# M212B.net
KiCad netlist of a schematic drawn in EAGLE
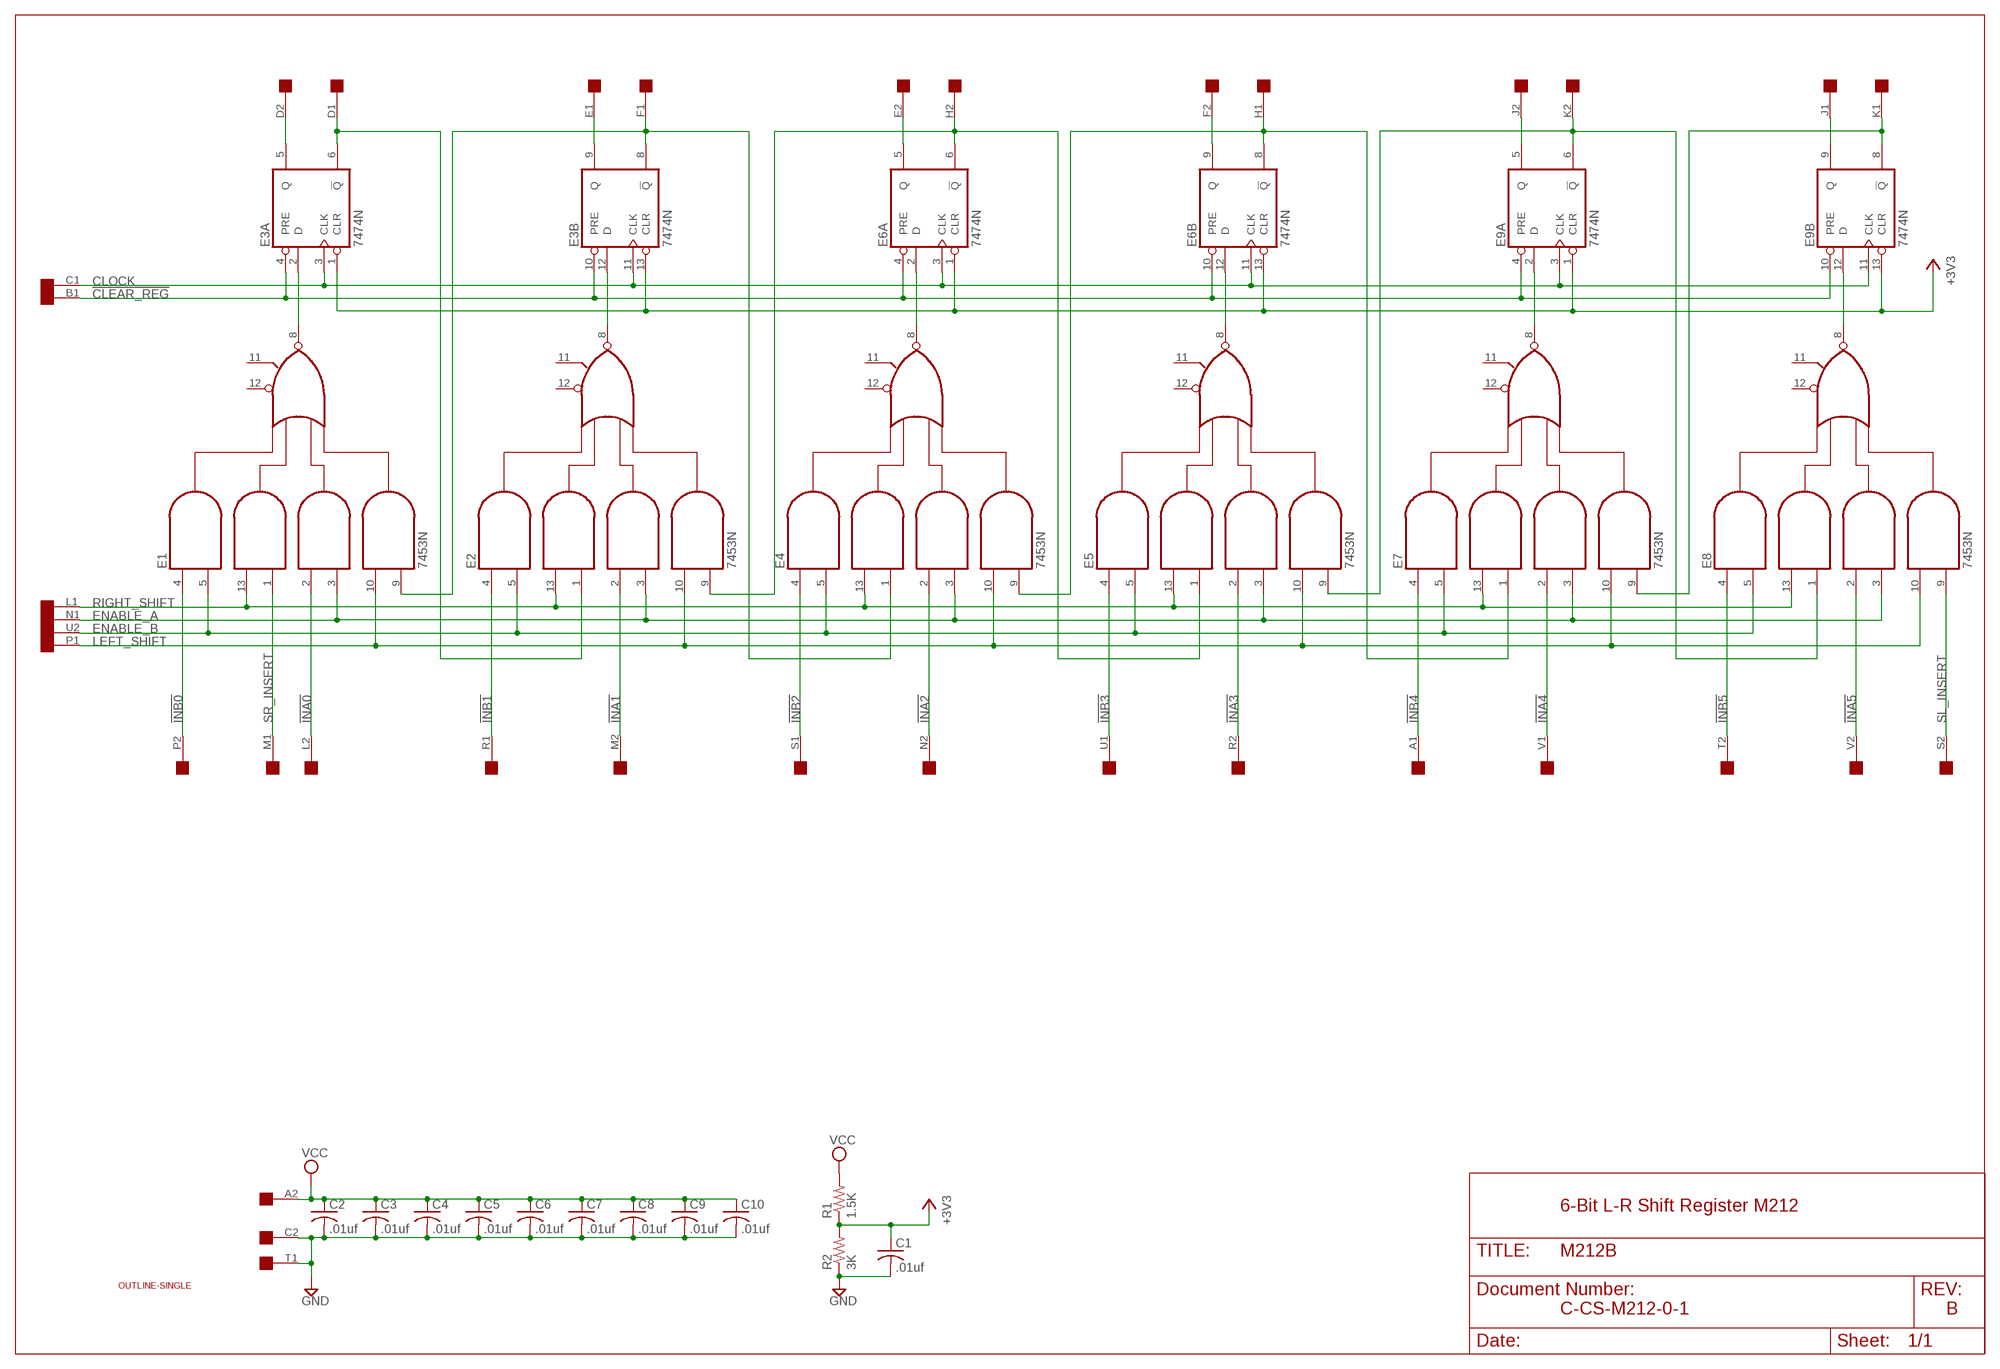
[diagram p0: schematic, sheet 1]

(export (version "E")
  (design (tool "Eeschema 10.0.6"))
  (components
    (comp (ref "C1")
      (value ".01uf")
      (footprint "eagle-import:C050-025X075")
      (libsource (lib "eagle-import") (part "C-US050-025X075"))
    )
    (comp (ref "C2")
      (value ".01uf")
      (footprint "eagle-import:C075-032X103")
      (libsource (lib "eagle-import") (part "C-US075-032X103"))
    )
    (comp (ref "C3")
      (value ".01uf")
      (footprint "eagle-import:C075-032X103")
      (libsource (lib "eagle-import") (part "C-US075-032X103"))
    )
    (comp (ref "C4")
      (value ".01uf")
      (footprint "eagle-import:C075-032X103")
      (libsource (lib "eagle-import") (part "C-US075-032X103"))
    )
    (comp (ref "C5")
      (value ".01uf")
      (footprint "eagle-import:C075-032X103")
      (libsource (lib "eagle-import") (part "C-US075-032X103"))
    )
    (comp (ref "C6")
      (value ".01uf")
      (footprint "eagle-import:C075-032X103")
      (libsource (lib "eagle-import") (part "C-US075-032X103"))
    )
    (comp (ref "C7")
      (value ".01uf")
      (footprint "eagle-import:C075-032X103")
      (libsource (lib "eagle-import") (part "C-US075-032X103"))
    )
    (comp (ref "C8")
      (value ".01uf")
      (footprint "eagle-import:C075-032X103")
      (libsource (lib "eagle-import") (part "C-US075-032X103"))
    )
    (comp (ref "C9")
      (value ".01uf")
      (footprint "eagle-import:C075-032X103")
      (libsource (lib "eagle-import") (part "C-US075-032X103"))
    )
    (comp (ref "C10")
      (value ".01uf")
      (footprint "eagle-import:C075-032X103")
      (libsource (lib "eagle-import") (part "C-US075-032X103"))
    )
    (comp (ref "E1")
      (value "7453N")
      (footprint "eagle-import:DIL14")
      (libsource (lib "eagle-import") (part "7453N"))
    )
    (comp (ref "E2")
      (value "7453N")
      (footprint "eagle-import:DIL14")
      (libsource (lib "eagle-import") (part "7453N"))
    )
    (comp (ref "E3")
      (value "7474N")
      (footprint "eagle-import:DIL14")
      (libsource (lib "eagle-import") (part "7474NS"))
    )
    (comp (ref "E4")
      (value "7453N")
      (footprint "eagle-import:DIL14")
      (libsource (lib "eagle-import") (part "7453N"))
    )
    (comp (ref "E5")
      (value "7453N")
      (footprint "eagle-import:DIL14")
      (libsource (lib "eagle-import") (part "7453N"))
    )
    (comp (ref "E6")
      (value "7474N")
      (footprint "eagle-import:DIL14")
      (libsource (lib "eagle-import") (part "7474NS"))
    )
    (comp (ref "E7")
      (value "7453N")
      (footprint "eagle-import:DIL14")
      (libsource (lib "eagle-import") (part "7453N"))
    )
    (comp (ref "E8")
      (value "7453N")
      (footprint "eagle-import:DIL14")
      (libsource (lib "eagle-import") (part "7453N"))
    )
    (comp (ref "E9")
      (value "7474N")
      (footprint "eagle-import:DIL14")
      (libsource (lib "eagle-import") (part "7474NS"))
    )
    (comp (ref "EDGE1")
      (value "EDGE-2CONNECTOR")
      (footprint "eagle-import:EDGE-CON2")
      (libsource (lib "eagle-import") (part "EDGE-2CONNECTOR"))
    )
    (comp (ref "R1")
      (value "1.5K")
      (footprint "eagle-import:0207_10")
      (libsource (lib "eagle-import") (part "R-US_0207/10"))
    )
    (comp (ref "R2")
      (value "3K")
      (footprint "eagle-import:0207_10")
      (libsource (lib "eagle-import") (part "R-US_0207/10"))
    )
    (comp (ref "U$1")
      (value "OUTLINE-SINGLE")
      (footprint "eagle-import:SINGLE")
      (libsource (lib "eagle-import") (part "OUTLINE-SINGLE"))
    )
  )
  (nets
    (net (code "1") (name "+3V3") (class "Default")
      (node (ref "C1") (pin "1") (pinfunction "1_1") (pintype "passive"))
      (node (ref "E3") (pin "1") (pinfunction "CLR_1") (pintype "input"))
      (node (ref "E3") (pin "13") (pinfunction "CLR_13") (pintype "input"))
      (node (ref "E6") (pin "1") (pinfunction "CLR_1") (pintype "input"))
      (node (ref "E6") (pin "13") (pinfunction "CLR_13") (pintype "input"))
      (node (ref "E9") (pin "1") (pinfunction "CLR_1") (pintype "input"))
      (node (ref "E9") (pin "13") (pinfunction "CLR_13") (pintype "input"))
      (node (ref "R1") (pin "1") (pinfunction "1_1") (pintype "passive"))
      (node (ref "R2") (pin "2") (pinfunction "2_2") (pintype "passive"))
    )
    (net (code "2") (name "/CLOCK") (class "Default")
      (node (ref "E3") (pin "11") (pinfunction "CLK_11") (pintype "input"))
      (node (ref "E3") (pin "3") (pinfunction "CLK_3") (pintype "input"))
      (node (ref "E6") (pin "11") (pinfunction "CLK_11") (pintype "input"))
      (node (ref "E6") (pin "3") (pinfunction "CLK_3") (pintype "input"))
      (node (ref "E9") (pin "11") (pinfunction "CLK_11") (pintype "input"))
      (node (ref "E9") (pin "3") (pinfunction "CLK_3") (pintype "input"))
      (node (ref "EDGE1") (pin "C1") (pinfunction "1_C1") (pintype "bidirectional"))
    )
    (net (code "3") (name "/ENABLE_A") (class "Default")
      (node (ref "E1") (pin "3") (pinfunction "I6_3") (pintype "input"))
      (node (ref "E2") (pin "3") (pinfunction "I6_3") (pintype "input"))
      (node (ref "E4") (pin "3") (pinfunction "I6_3") (pintype "input"))
      (node (ref "E5") (pin "3") (pinfunction "I6_3") (pintype "input"))
      (node (ref "E7") (pin "3") (pinfunction "I6_3") (pintype "input"))
      (node (ref "E8") (pin "3") (pinfunction "I6_3") (pintype "input"))
      (node (ref "EDGE1") (pin "N1") (pinfunction "1_N1") (pintype "bidirectional"))
    )
    (net (code "4") (name "/ENABLE_B") (class "Default")
      (node (ref "E1") (pin "5") (pinfunction "I2_5") (pintype "input"))
      (node (ref "E2") (pin "5") (pinfunction "I2_5") (pintype "input"))
      (node (ref "E4") (pin "5") (pinfunction "I2_5") (pintype "input"))
      (node (ref "E5") (pin "5") (pinfunction "I2_5") (pintype "input"))
      (node (ref "E7") (pin "5") (pinfunction "I2_5") (pintype "input"))
      (node (ref "E8") (pin "5") (pinfunction "I2_5") (pintype "input"))
      (node (ref "EDGE1") (pin "U2") (pinfunction "1_U2") (pintype "bidirectional"))
    )
    (net (code "5") (name "/LEFT_SHIFT") (class "Default")
      (node (ref "E1") (pin "10") (pinfunction "I7_10") (pintype "input"))
      (node (ref "E2") (pin "10") (pinfunction "I7_10") (pintype "input"))
      (node (ref "E4") (pin "10") (pinfunction "I7_10") (pintype "input"))
      (node (ref "E5") (pin "10") (pinfunction "I7_10") (pintype "input"))
      (node (ref "E7") (pin "10") (pinfunction "I7_10") (pintype "input"))
      (node (ref "E8") (pin "10") (pinfunction "I7_10") (pintype "input"))
      (node (ref "EDGE1") (pin "P1") (pinfunction "1_P1") (pintype "bidirectional"))
    )
    (net (code "6") (name "/RIGHT_SHIFT") (class "Default")
      (node (ref "E1") (pin "13") (pinfunction "I3_13") (pintype "input"))
      (node (ref "E2") (pin "13") (pinfunction "I3_13") (pintype "input"))
      (node (ref "E4") (pin "13") (pinfunction "I3_13") (pintype "input"))
      (node (ref "E5") (pin "13") (pinfunction "I3_13") (pintype "input"))
      (node (ref "E7") (pin "13") (pinfunction "I3_13") (pintype "input"))
      (node (ref "E8") (pin "13") (pinfunction "I3_13") (pintype "input"))
      (node (ref "EDGE1") (pin "L1") (pinfunction "1_L1") (pintype "bidirectional"))
    )
    (net (code "7") (name "/SL_INSERT") (class "Default")
      (node (ref "E8") (pin "9") (pinfunction "I8_9") (pintype "input"))
      (node (ref "EDGE1") (pin "S2") (pinfunction "1_S2") (pintype "bidirectional"))
    )
    (net (code "8") (name "/SR_INSERT") (class "Default")
      (node (ref "E1") (pin "1") (pinfunction "I4_1") (pintype "input"))
      (node (ref "EDGE1") (pin "M1") (pinfunction "1_M1") (pintype "bidirectional"))
    )
    (net (code "9") (name "/~{CLEAR_REG}") (class "Default")
      (node (ref "E3") (pin "10") (pinfunction "PRE_10") (pintype "input"))
      (node (ref "E3") (pin "4") (pinfunction "PRE_4") (pintype "input"))
      (node (ref "E6") (pin "10") (pinfunction "PRE_10") (pintype "input"))
      (node (ref "E6") (pin "4") (pinfunction "PRE_4") (pintype "input"))
      (node (ref "E9") (pin "10") (pinfunction "PRE_10") (pintype "input"))
      (node (ref "E9") (pin "4") (pinfunction "PRE_4") (pintype "input"))
      (node (ref "EDGE1") (pin "B1") (pinfunction "1_B1") (pintype "bidirectional"))
    )
    (net (code "10") (name "/~{INA0}") (class "Default")
      (node (ref "E1") (pin "2") (pinfunction "I5_2") (pintype "input"))
      (node (ref "EDGE1") (pin "L2") (pinfunction "1_L2") (pintype "bidirectional"))
    )
    (net (code "11") (name "/~{INA1}") (class "Default")
      (node (ref "E2") (pin "2") (pinfunction "I5_2") (pintype "input"))
      (node (ref "EDGE1") (pin "M2") (pinfunction "1_M2") (pintype "bidirectional"))
    )
    (net (code "12") (name "/~{INA2}") (class "Default")
      (node (ref "E4") (pin "2") (pinfunction "I5_2") (pintype "input"))
      (node (ref "EDGE1") (pin "N2") (pinfunction "1_N2") (pintype "bidirectional"))
    )
    (net (code "13") (name "/~{INA3}") (class "Default")
      (node (ref "E5") (pin "2") (pinfunction "I5_2") (pintype "input"))
      (node (ref "EDGE1") (pin "R2") (pinfunction "1_R2") (pintype "bidirectional"))
    )
    (net (code "14") (name "/~{INA4}") (class "Default")
      (node (ref "E7") (pin "2") (pinfunction "I5_2") (pintype "input"))
      (node (ref "EDGE1") (pin "V1") (pinfunction "1_V1") (pintype "bidirectional"))
    )
    (net (code "15") (name "/~{INA5}") (class "Default")
      (node (ref "E8") (pin "2") (pinfunction "I5_2") (pintype "input"))
      (node (ref "EDGE1") (pin "V2") (pinfunction "1_V2") (pintype "bidirectional"))
    )
    (net (code "16") (name "/~{INB0}") (class "Default")
      (node (ref "E1") (pin "4") (pinfunction "I1_4") (pintype "input"))
      (node (ref "EDGE1") (pin "P2") (pinfunction "1_P2") (pintype "bidirectional"))
    )
    (net (code "17") (name "/~{INB1}") (class "Default")
      (node (ref "E2") (pin "4") (pinfunction "I1_4") (pintype "input"))
      (node (ref "EDGE1") (pin "R1") (pinfunction "1_R1") (pintype "bidirectional"))
    )
    (net (code "18") (name "/~{INB2}") (class "Default")
      (node (ref "E4") (pin "4") (pinfunction "I1_4") (pintype "input"))
      (node (ref "EDGE1") (pin "S1") (pinfunction "1_S1") (pintype "bidirectional"))
    )
    (net (code "19") (name "/~{INB3}") (class "Default")
      (node (ref "E5") (pin "4") (pinfunction "I1_4") (pintype "input"))
      (node (ref "EDGE1") (pin "U1") (pinfunction "1_U1") (pintype "bidirectional"))
    )
    (net (code "20") (name "/~{INB4}") (class "Default")
      (node (ref "E7") (pin "4") (pinfunction "I1_4") (pintype "input"))
      (node (ref "EDGE1") (pin "A1") (pinfunction "1_A1") (pintype "bidirectional"))
    )
    (net (code "21") (name "/~{INB5}") (class "Default")
      (node (ref "E8") (pin "4") (pinfunction "I1_4") (pintype "input"))
      (node (ref "EDGE1") (pin "T2") (pinfunction "1_T2") (pintype "bidirectional"))
    )
    (net (code "22") (name "GND") (class "Default")
      (node (ref "C1") (pin "2") (pinfunction "2_2") (pintype "passive"))
      (node (ref "C10") (pin "2") (pinfunction "2_2") (pintype "passive"))
      (node (ref "C2") (pin "2") (pinfunction "2_2") (pintype "passive"))
      (node (ref "C3") (pin "2") (pinfunction "2_2") (pintype "passive"))
      (node (ref "C4") (pin "2") (pinfunction "2_2") (pintype "passive"))
      (node (ref "C5") (pin "2") (pinfunction "2_2") (pintype "passive"))
      (node (ref "C6") (pin "2") (pinfunction "2_2") (pintype "passive"))
      (node (ref "C7") (pin "2") (pinfunction "2_2") (pintype "passive"))
      (node (ref "C8") (pin "2") (pinfunction "2_2") (pintype "passive"))
      (node (ref "C9") (pin "2") (pinfunction "2_2") (pintype "passive"))
      (node (ref "EDGE1") (pin "C2") (pinfunction "1_C2") (pintype "bidirectional"))
      (node (ref "EDGE1") (pin "T1") (pinfunction "1_T1") (pintype "bidirectional"))
      (node (ref "R2") (pin "1") (pinfunction "1_1") (pintype "passive"))
    )
    (net (code "23") (name "Net-(E1A-I8)") (class "Default")
      (node (ref "E1") (pin "9") (pinfunction "I8_9") (pintype "input"))
      (node (ref "E3") (pin "8") (pinfunction "~{Q}_8") (pintype "output"))
      (node (ref "E4") (pin "1") (pinfunction "I4_1") (pintype "input"))
      (node (ref "EDGE1") (pin "F1") (pinfunction "1_F1") (pintype "bidirectional"))
    )
    (net (code "24") (name "Net-(E1A-O)") (class "Default")
      (node (ref "E1") (pin "8") (pinfunction "O_8") (pintype "output"))
      (node (ref "E3") (pin "2") (pinfunction "D_2") (pintype "input"))
    )
    (net (code "25") (name "Net-(E2A-I4)") (class "Default")
      (node (ref "E2") (pin "1") (pinfunction "I4_1") (pintype "input"))
      (node (ref "E3") (pin "6") (pinfunction "~{Q}_6") (pintype "output"))
      (node (ref "EDGE1") (pin "D1") (pinfunction "1_D1") (pintype "bidirectional"))
    )
    (net (code "26") (name "Net-(E2A-I8)") (class "Default")
      (node (ref "E2") (pin "9") (pinfunction "I8_9") (pintype "input"))
      (node (ref "E5") (pin "1") (pinfunction "I4_1") (pintype "input"))
      (node (ref "E6") (pin "6") (pinfunction "~{Q}_6") (pintype "output"))
      (node (ref "EDGE1") (pin "H2") (pinfunction "1_H2") (pintype "bidirectional"))
    )
    (net (code "27") (name "Net-(E2A-O)") (class "Default")
      (node (ref "E2") (pin "8") (pinfunction "O_8") (pintype "output"))
      (node (ref "E3") (pin "12") (pinfunction "D_12") (pintype "input"))
    )
    (net (code "28") (name "Net-(E3A-Q)") (class "Default")
      (node (ref "E3") (pin "5") (pinfunction "Q_5") (pintype "output"))
      (node (ref "EDGE1") (pin "D2") (pinfunction "1_D2") (pintype "bidirectional"))
    )
    (net (code "29") (name "Net-(E3B-Q)") (class "Default")
      (node (ref "E3") (pin "9") (pinfunction "Q_9") (pintype "output"))
      (node (ref "EDGE1") (pin "E1") (pinfunction "1_E1") (pintype "bidirectional"))
    )
    (net (code "30") (name "Net-(E4A-I8)") (class "Default")
      (node (ref "E4") (pin "9") (pinfunction "I8_9") (pintype "input"))
      (node (ref "E6") (pin "8") (pinfunction "~{Q}_8") (pintype "output"))
      (node (ref "E7") (pin "1") (pinfunction "I4_1") (pintype "input"))
      (node (ref "EDGE1") (pin "H1") (pinfunction "1_H1") (pintype "bidirectional"))
    )
    (net (code "31") (name "Net-(E4A-O)") (class "Default")
      (node (ref "E4") (pin "8") (pinfunction "O_8") (pintype "output"))
      (node (ref "E6") (pin "2") (pinfunction "D_2") (pintype "input"))
    )
    (net (code "32") (name "Net-(E5A-I8)") (class "Default")
      (node (ref "E5") (pin "9") (pinfunction "I8_9") (pintype "input"))
      (node (ref "E8") (pin "1") (pinfunction "I4_1") (pintype "input"))
      (node (ref "E9") (pin "6") (pinfunction "~{Q}_6") (pintype "output"))
      (node (ref "EDGE1") (pin "K2") (pinfunction "1_K2") (pintype "bidirectional"))
    )
    (net (code "33") (name "Net-(E5A-O)") (class "Default")
      (node (ref "E5") (pin "8") (pinfunction "O_8") (pintype "output"))
      (node (ref "E6") (pin "12") (pinfunction "D_12") (pintype "input"))
    )
    (net (code "34") (name "Net-(E6A-Q)") (class "Default")
      (node (ref "E6") (pin "5") (pinfunction "Q_5") (pintype "output"))
      (node (ref "EDGE1") (pin "E2") (pinfunction "1_E2") (pintype "bidirectional"))
    )
    (net (code "35") (name "Net-(E6B-Q)") (class "Default")
      (node (ref "E6") (pin "9") (pinfunction "Q_9") (pintype "output"))
      (node (ref "EDGE1") (pin "F2") (pinfunction "1_F2") (pintype "bidirectional"))
    )
    (net (code "36") (name "Net-(E7A-I8)") (class "Default")
      (node (ref "E7") (pin "9") (pinfunction "I8_9") (pintype "input"))
      (node (ref "E9") (pin "8") (pinfunction "~{Q}_8") (pintype "output"))
      (node (ref "EDGE1") (pin "K1") (pinfunction "1_K1") (pintype "bidirectional"))
    )
    (net (code "37") (name "Net-(E7A-O)") (class "Default")
      (node (ref "E7") (pin "8") (pinfunction "O_8") (pintype "output"))
      (node (ref "E9") (pin "2") (pinfunction "D_2") (pintype "input"))
    )
    (net (code "38") (name "Net-(E8A-O)") (class "Default")
      (node (ref "E8") (pin "8") (pinfunction "O_8") (pintype "output"))
      (node (ref "E9") (pin "12") (pinfunction "D_12") (pintype "input"))
    )
    (net (code "39") (name "Net-(E9A-Q)") (class "Default")
      (node (ref "E9") (pin "5") (pinfunction "Q_5") (pintype "output"))
      (node (ref "EDGE1") (pin "J2") (pinfunction "1_J2") (pintype "bidirectional"))
    )
    (net (code "40") (name "Net-(E9B-Q)") (class "Default")
      (node (ref "E9") (pin "9") (pinfunction "Q_9") (pintype "output"))
      (node (ref "EDGE1") (pin "J1") (pinfunction "1_J1") (pintype "bidirectional"))
    )
    (net (code "41") (name "VCC") (class "Default")
      (node (ref "C10") (pin "1") (pinfunction "1_1") (pintype "passive"))
      (node (ref "C2") (pin "1") (pinfunction "1_1") (pintype "passive"))
      (node (ref "C3") (pin "1") (pinfunction "1_1") (pintype "passive"))
      (node (ref "C4") (pin "1") (pinfunction "1_1") (pintype "passive"))
      (node (ref "C5") (pin "1") (pinfunction "1_1") (pintype "passive"))
      (node (ref "C6") (pin "1") (pinfunction "1_1") (pintype "passive"))
      (node (ref "C7") (pin "1") (pinfunction "1_1") (pintype "passive"))
      (node (ref "C8") (pin "1") (pinfunction "1_1") (pintype "passive"))
      (node (ref "C9") (pin "1") (pinfunction "1_1") (pintype "passive"))
      (node (ref "EDGE1") (pin "A2") (pinfunction "1_A2") (pintype "bidirectional"))
      (node (ref "R1") (pin "2") (pinfunction "2_2") (pintype "passive"))
    )
    (net (code "42") (name "unconnected-(E1A-I9-Pad12)") (class "Default")
      (node (ref "E1") (pin "12") (pinfunction "I9_12") (pintype "passive"))
    )
    (net (code "43") (name "unconnected-(E1A-I10-Pad11)") (class "Default")
      (node (ref "E1") (pin "11") (pinfunction "I10_11") (pintype "passive"))
    )
    (net (code "44") (name "unconnected-(E2A-I9-Pad12)") (class "Default")
      (node (ref "E2") (pin "12") (pinfunction "I9_12") (pintype "passive"))
    )
    (net (code "45") (name "unconnected-(E2A-I10-Pad11)") (class "Default")
      (node (ref "E2") (pin "11") (pinfunction "I10_11") (pintype "passive"))
    )
    (net (code "46") (name "unconnected-(E4A-I9-Pad12)") (class "Default")
      (node (ref "E4") (pin "12") (pinfunction "I9_12") (pintype "passive"))
    )
    (net (code "47") (name "unconnected-(E4A-I10-Pad11)") (class "Default")
      (node (ref "E4") (pin "11") (pinfunction "I10_11") (pintype "passive"))
    )
    (net (code "48") (name "unconnected-(E5A-I9-Pad12)") (class "Default")
      (node (ref "E5") (pin "12") (pinfunction "I9_12") (pintype "passive"))
    )
    (net (code "49") (name "unconnected-(E5A-I10-Pad11)") (class "Default")
      (node (ref "E5") (pin "11") (pinfunction "I10_11") (pintype "passive"))
    )
    (net (code "50") (name "unconnected-(E7A-I9-Pad12)") (class "Default")
      (node (ref "E7") (pin "12") (pinfunction "I9_12") (pintype "passive"))
    )
    (net (code "51") (name "unconnected-(E7A-I10-Pad11)") (class "Default")
      (node (ref "E7") (pin "11") (pinfunction "I10_11") (pintype "passive"))
    )
    (net (code "52") (name "unconnected-(E8A-I9-Pad12)") (class "Default")
      (node (ref "E8") (pin "12") (pinfunction "I9_12") (pintype "passive"))
    )
    (net (code "53") (name "unconnected-(E8A-I10-Pad11)") (class "Default")
      (node (ref "E8") (pin "11") (pinfunction "I10_11") (pintype "passive"))
    )
  )
)
